# Picobox.net
KiCad netlist of a schematic drawn in EasyEDA
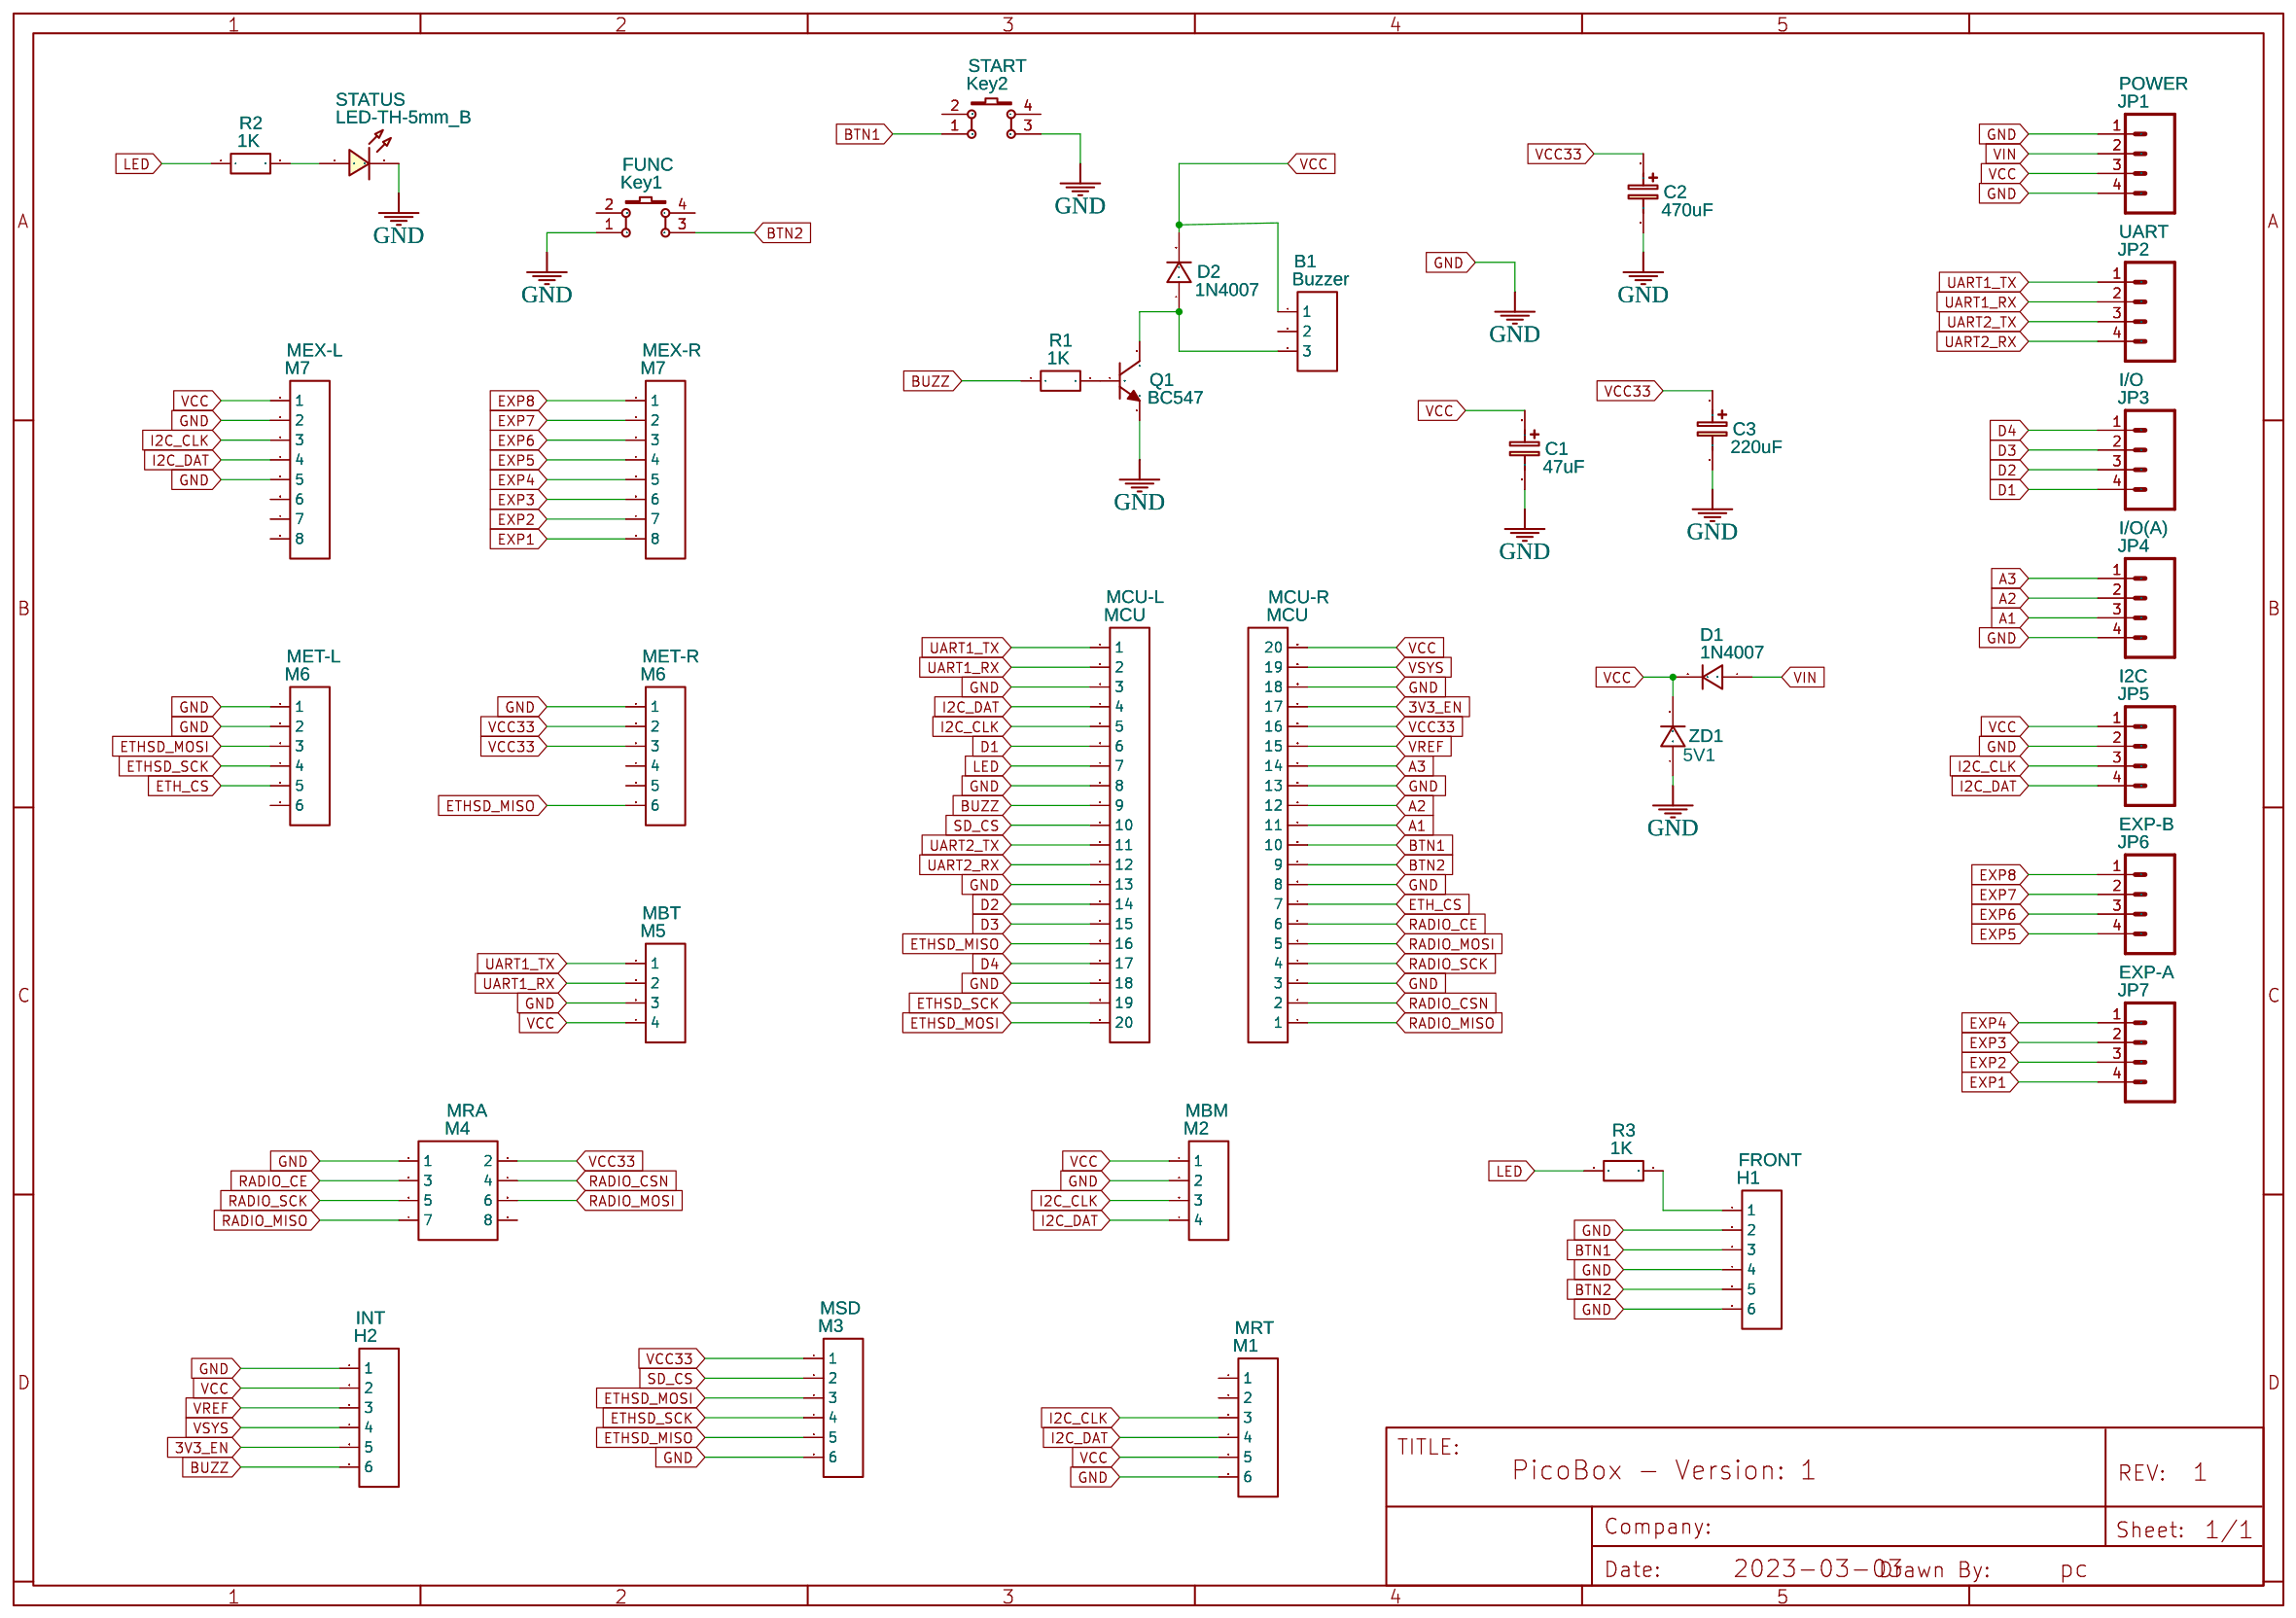
[diagram p0: schematic sheet]

(export (version "E")
  (design (tool "Eeschema 10.0.6"))
  (components
    (comp (ref "B1")
      (value "Buzzer")
      (fields (field (name "BOM_Supplier Part") "C146690"))
      (libsource (lib "") (part "HDR-F-2.54_1x3"))
    )
    (comp (ref "C1") (value "47uF") (libsource (lib "") (part "C_Tan_SMD_A_EU")))
    (comp (ref "C2") (value "470uF") (libsource (lib "") (part "C_Tan_SMD_A_EU")))
    (comp (ref "C3") (value "220uF") (libsource (lib "") (part "C_Tan_SMD_A_EU")))
    (comp (ref "D1")
      (value "1N4007")
      (fields (field (name "BOM_Manufacturer Part") "1N4007W") (field (name "BOM_Supplier Part") "C328592"))
      (libsource (lib "") (part "1N4007W_2"))
    )
    (comp (ref "D2")
      (value "1N4007")
      (fields (field (name "BOM_Manufacturer Part") "1N4007W") (field (name "BOM_Supplier Part") "C328592"))
      (libsource (lib "") (part "1N4007W_1"))
    )
    (comp (ref "EXP-A") (value "JP7") (libsource (lib "") (part "M04SCREW_5")))
    (comp (ref "EXP-B") (value "JP6") (libsource (lib "") (part "M04SCREW_2")))
    (comp (ref "FRONT")
      (value "H1")
      (fields (field (name "BOM_Supplier Part") "C40877"))
      (libsource (lib "") (part "HDR-F-2.54_1x6_3"))
    )
    (comp (ref "FUNC")
      (value "Key1")
      (fields
        (field (name "BOM_Manufacturer Part") "K2-1102DP-E4SW-04")
        (field (name "BOM_Supplier Part") "C136684")
      )
      (libsource (lib "") (part "K4-6×6_TH"))
    )
    (comp (ref "I/O") (value "JP3") (libsource (lib "") (part "M04SCREW_3")))
    (comp (ref "I/O(A)") (value "JP4") (libsource (lib "") (part "M04SCREW")))
    (comp (ref "I2C") (value "JP5") (libsource (lib "") (part "M04SCREW_1")))
    (comp (ref "INT")
      (value "H2")
      (fields (field (name "BOM_Supplier Part") "C40877"))
      (libsource (lib "") (part "HDR-F-2.54_1x6_4"))
    )
    (comp (ref "MBM")
      (value "M2")
      (fields (field (name "BOM_Supplier Part") "C225501"))
      (libsource (lib "") (part "HDR-F-2.54_1x4_1"))
    )
    (comp (ref "MBT")
      (value "M5")
      (fields (field (name "BOM_Supplier Part") "C225501"))
      (libsource (lib "") (part "HDR-F-2.54_1x4"))
    )
    (comp (ref "MCU-L")
      (value "MCU")
      (fields (field (name "BOM_Supplier Part") "C50984"))
      (libsource (lib "") (part "HDR-F-2.54_1x20_1"))
    )
    (comp (ref "MCU-R")
      (value "MCU")
      (fields (field (name "BOM_Supplier Part") "C50984"))
      (libsource (lib "") (part "HDR-F-2.54_1x20"))
    )
    (comp (ref "MET-L")
      (value "M6")
      (fields (field (name "BOM_Supplier Part") "C40877"))
      (libsource (lib "") (part "HDR-F-2.54_1x6_1"))
    )
    (comp (ref "MET-R")
      (value "M6")
      (fields (field (name "BOM_Supplier Part") "C40877"))
      (libsource (lib "") (part "HDR-F-2.54_1x6_5"))
    )
    (comp (ref "MEX-L")
      (value "M7")
      (fields (field (name "BOM_Supplier Part") "C225505"))
      (libsource (lib "") (part "HDR-F-2.54_1x8_1"))
    )
    (comp (ref "MEX-R")
      (value "M7")
      (fields (field (name "BOM_Supplier Part") "C225505"))
      (libsource (lib "") (part "HDR-F-2.54_1x8"))
    )
    (comp (ref "MRA")
      (value "M4")
      (fields (field (name "BOM_Supplier Part") "C239344"))
      (libsource (lib "") (part "HDR-F-2.54_2x4"))
    )
    (comp (ref "MRT")
      (value "M1")
      (fields (field (name "BOM_Supplier Part") "C40877"))
      (libsource (lib "") (part "HDR-F-2.54_1x6"))
    )
    (comp (ref "MSD")
      (value "M3")
      (fields (field (name "BOM_Supplier Part") "C40877"))
      (libsource (lib "") (part "HDR-F-2.54_1x6_2"))
    )
    (comp (ref "POWER") (value "JP1") (libsource (lib "") (part "M04SCREW_6")))
    (comp (ref "Q1")
      (value "BC547")
      (fields
        (field (name "BOM_Manufacturer Part") "2n3904S-RTK/PS")
        (field (name "BOM_Supplier Part") "C18536")
      )
      (libsource (lib "") (part "2N3904(SOT-23)"))
    )
    (comp (ref "R1") (value "1K") (libsource (lib "") (part "R_0603_EU")))
    (comp (ref "R2") (value "1K") (libsource (lib "") (part "R_0603_EU")))
    (comp (ref "R3") (value "1K") (libsource (lib "") (part "R_0603_EU")))
    (comp (ref "START")
      (value "Key2")
      (fields
        (field (name "BOM_Manufacturer Part") "K2-1102DP-E4SW-04")
        (field (name "BOM_Supplier Part") "C136684")
      )
      (libsource (lib "") (part "K4-6×6_TH_1"))
    )
    (comp (ref "STATUS")
      (value "LED-TH-5mm_B")
      (fields
        (field (name "BOM_Manufacturer Part") "333-2SYGD/S530-E2")
        (field (name "BOM_Supplier Part") "C88163")
      )
      (libsource (lib "") (part "LED-TH-5mm_G"))
    )
    (comp (ref "UART") (value "JP2") (libsource (lib "") (part "M04SCREW_4")))
    (comp (ref "ZD1")
      (value "1N4001")
      (fields (field (name "BOM_Manufacturer Part") "1N4007W") (field (name "BOM_Supplier Part") "C328592"))
      (libsource (lib "") (part "1N4007W"))
    )
  )
  (nets
    (net (code "1") (name "3V3_EN") (class "Default")
      (node (ref "INT") (pin "5") (pinfunction "5_5") (pintype "input"))
      (node (ref "MCU-R") (pin "17") (pinfunction "17_17") (pintype "unspecified"))
    )
    (net (code "2") (name "A1") (class "Default")
      (node (ref "I/O(A)") (pin "3") (pinfunction "3_3") (pintype "bidirectional"))
      (node (ref "MCU-R") (pin "11") (pinfunction "11_11") (pintype "unspecified"))
    )
    (net (code "3") (name "A2") (class "Default")
      (node (ref "I/O(A)") (pin "2") (pinfunction "2_2") (pintype "bidirectional"))
      (node (ref "MCU-R") (pin "12") (pinfunction "12_12") (pintype "unspecified"))
    )
    (net (code "4") (name "A3") (class "Default")
      (node (ref "I/O(A)") (pin "1") (pinfunction "1_1") (pintype "bidirectional"))
      (node (ref "MCU-R") (pin "14") (pinfunction "14_14") (pintype "unspecified"))
    )
    (net (code "5") (name "BTN1") (class "Default")
      (node (ref "FRONT") (pin "3") (pinfunction "3_3") (pintype "input"))
      (node (ref "MCU-R") (pin "10") (pinfunction "10_10") (pintype "unspecified"))
      (node (ref "START") (pin "1") (pinfunction "1_1") (pintype "unspecified"))
    )
    (net (code "6") (name "BTN2") (class "Default")
      (node (ref "FRONT") (pin "5") (pinfunction "5_5") (pintype "input"))
      (node (ref "FUNC") (pin "3") (pinfunction "3_3") (pintype "unspecified"))
      (node (ref "MCU-R") (pin "9") (pinfunction "9_9") (pintype "unspecified"))
    )
    (net (code "7") (name "BUZZ") (class "Default")
      (node (ref "INT") (pin "6") (pinfunction "6_6") (pintype "input"))
      (node (ref "MCU-L") (pin "9") (pinfunction "9_9") (pintype "unspecified"))
      (node (ref "R1") (pin "1") (pinfunction "1_1") (pintype "unspecified"))
    )
    (net (code "8") (name "D1") (class "Default")
      (node (ref "I/O") (pin "4") (pinfunction "4_4") (pintype "bidirectional"))
      (node (ref "MCU-L") (pin "6") (pinfunction "6_6") (pintype "unspecified"))
    )
    (net (code "9") (name "D2") (class "Default")
      (node (ref "I/O") (pin "3") (pinfunction "3_3") (pintype "bidirectional"))
      (node (ref "MCU-L") (pin "14") (pinfunction "14_14") (pintype "unspecified"))
    )
    (net (code "10") (name "D3") (class "Default")
      (node (ref "I/O") (pin "2") (pinfunction "2_2") (pintype "bidirectional"))
      (node (ref "MCU-L") (pin "15") (pinfunction "15_15") (pintype "unspecified"))
    )
    (net (code "11") (name "D4") (class "Default")
      (node (ref "I/O") (pin "1") (pinfunction "1_1") (pintype "bidirectional"))
      (node (ref "MCU-L") (pin "17") (pinfunction "17_17") (pintype "unspecified"))
    )
    (net (code "12") (name "ETHSD_MISO") (class "Default")
      (node (ref "MCU-L") (pin "16") (pinfunction "16_16") (pintype "unspecified"))
      (node (ref "MET-R") (pin "6") (pinfunction "6_6") (pintype "input"))
      (node (ref "MSD") (pin "5") (pinfunction "5_5") (pintype "input"))
    )
    (net (code "13") (name "ETHSD_MOSI") (class "Default")
      (node (ref "MCU-L") (pin "20") (pinfunction "20_20") (pintype "unspecified"))
      (node (ref "MET-L") (pin "3") (pinfunction "3_3") (pintype "input"))
      (node (ref "MSD") (pin "3") (pinfunction "3_3") (pintype "input"))
    )
    (net (code "14") (name "ETHSD_SCK") (class "Default")
      (node (ref "MCU-L") (pin "19") (pinfunction "19_19") (pintype "unspecified"))
      (node (ref "MET-L") (pin "4") (pinfunction "4_4") (pintype "input"))
      (node (ref "MSD") (pin "4") (pinfunction "4_4") (pintype "input"))
    )
    (net (code "15") (name "ETH_CS") (class "Default")
      (node (ref "MCU-R") (pin "7") (pinfunction "7_7") (pintype "unspecified"))
      (node (ref "MET-L") (pin "5") (pinfunction "5_5") (pintype "input"))
    )
    (net (code "16") (name "EXP1") (class "Default")
      (node (ref "EXP-A") (pin "4") (pinfunction "4_4") (pintype "bidirectional"))
      (node (ref "MEX-R") (pin "8") (pinfunction "8_8") (pintype "unspecified"))
    )
    (net (code "17") (name "EXP2") (class "Default")
      (node (ref "EXP-A") (pin "3") (pinfunction "3_3") (pintype "bidirectional"))
      (node (ref "MEX-R") (pin "7") (pinfunction "7_7") (pintype "unspecified"))
    )
    (net (code "18") (name "EXP3") (class "Default")
      (node (ref "EXP-A") (pin "2") (pinfunction "2_2") (pintype "bidirectional"))
      (node (ref "MEX-R") (pin "6") (pinfunction "6_6") (pintype "unspecified"))
    )
    (net (code "19") (name "EXP4") (class "Default")
      (node (ref "EXP-A") (pin "1") (pinfunction "1_1") (pintype "bidirectional"))
      (node (ref "MEX-R") (pin "5") (pinfunction "5_5") (pintype "unspecified"))
    )
    (net (code "20") (name "EXP5") (class "Default")
      (node (ref "EXP-B") (pin "4") (pinfunction "4_4") (pintype "bidirectional"))
      (node (ref "MEX-R") (pin "4") (pinfunction "4_4") (pintype "unspecified"))
    )
    (net (code "21") (name "EXP6") (class "Default")
      (node (ref "EXP-B") (pin "3") (pinfunction "3_3") (pintype "bidirectional"))
      (node (ref "MEX-R") (pin "3") (pinfunction "3_3") (pintype "unspecified"))
    )
    (net (code "22") (name "EXP7") (class "Default")
      (node (ref "EXP-B") (pin "2") (pinfunction "2_2") (pintype "bidirectional"))
      (node (ref "MEX-R") (pin "2") (pinfunction "2_2") (pintype "unspecified"))
    )
    (net (code "23") (name "EXP8") (class "Default")
      (node (ref "EXP-B") (pin "1") (pinfunction "1_1") (pintype "bidirectional"))
      (node (ref "MEX-R") (pin "1") (pinfunction "1_1") (pintype "unspecified"))
    )
    (net (code "24") (name "GND") (class "Default")
      (node (ref "C1") (pin "VSS") (pinfunction "2_VSS") (pintype "unspecified"))
      (node (ref "C2") (pin "VSS") (pinfunction "2_VSS") (pintype "unspecified"))
      (node (ref "C3") (pin "VSS") (pinfunction "2_VSS") (pintype "unspecified"))
      (node (ref "FRONT") (pin "2") (pinfunction "2_2") (pintype "input"))
      (node (ref "FRONT") (pin "4") (pinfunction "4_4") (pintype "input"))
      (node (ref "FRONT") (pin "6") (pinfunction "6_6") (pintype "input"))
      (node (ref "FUNC") (pin "1") (pinfunction "1_1") (pintype "unspecified"))
      (node (ref "I/O(A)") (pin "4") (pinfunction "4_4") (pintype "bidirectional"))
      (node (ref "I2C") (pin "2") (pinfunction "2_2") (pintype "bidirectional"))
      (node (ref "INT") (pin "1") (pinfunction "1_1") (pintype "input"))
      (node (ref "MBM") (pin "2") (pinfunction "2_2") (pintype "unspecified"))
      (node (ref "MBT") (pin "3") (pinfunction "3_3") (pintype "unspecified"))
      (node (ref "MCU-L") (pin "13") (pinfunction "13_13") (pintype "unspecified"))
      (node (ref "MCU-L") (pin "18") (pinfunction "18_18") (pintype "unspecified"))
      (node (ref "MCU-L") (pin "3") (pinfunction "3_3") (pintype "unspecified"))
      (node (ref "MCU-L") (pin "8") (pinfunction "8_8") (pintype "unspecified"))
      (node (ref "MCU-R") (pin "13") (pinfunction "13_13") (pintype "unspecified"))
      (node (ref "MCU-R") (pin "18") (pinfunction "18_18") (pintype "unspecified"))
      (node (ref "MCU-R") (pin "3") (pinfunction "3_3") (pintype "unspecified"))
      (node (ref "MCU-R") (pin "8") (pinfunction "8_8") (pintype "unspecified"))
      (node (ref "MET-L") (pin "1") (pinfunction "1_1") (pintype "input"))
      (node (ref "MET-L") (pin "2") (pinfunction "2_2") (pintype "input"))
      (node (ref "MET-R") (pin "1") (pinfunction "1_1") (pintype "input"))
      (node (ref "MEX-L") (pin "2") (pinfunction "2_2") (pintype "unspecified"))
      (node (ref "MEX-L") (pin "5") (pinfunction "5_5") (pintype "unspecified"))
      (node (ref "MRA") (pin "1") (pinfunction "1_1") (pintype "unspecified"))
      (node (ref "MRT") (pin "6") (pinfunction "6_6") (pintype "input"))
      (node (ref "MSD") (pin "6") (pinfunction "6_6") (pintype "input"))
      (node (ref "POWER") (pin "1") (pinfunction "1_1") (pintype "bidirectional"))
      (node (ref "POWER") (pin "4") (pinfunction "4_4") (pintype "bidirectional"))
      (node (ref "Q1") (pin "1") (pinfunction "E_1") (pintype "input"))
      (node (ref "START") (pin "3") (pinfunction "3_3") (pintype "unspecified"))
      (node (ref "STATUS") (pin "2") (pinfunction "2_2") (pintype "unspecified"))
      (node (ref "ZD1") (pin "A") (pinfunction "2_A") (pintype "unspecified"))
    )
    (net (code "25") (name "I2C_CLK") (class "Default")
      (node (ref "I2C") (pin "3") (pinfunction "3_3") (pintype "bidirectional"))
      (node (ref "MBM") (pin "3") (pinfunction "3_3") (pintype "unspecified"))
      (node (ref "MCU-L") (pin "5") (pinfunction "5_5") (pintype "unspecified"))
      (node (ref "MEX-L") (pin "3") (pinfunction "3_3") (pintype "unspecified"))
      (node (ref "MRT") (pin "3") (pinfunction "3_3") (pintype "input"))
    )
    (net (code "26") (name "I2C_DAT") (class "Default")
      (node (ref "I2C") (pin "4") (pinfunction "4_4") (pintype "bidirectional"))
      (node (ref "MBM") (pin "4") (pinfunction "4_4") (pintype "unspecified"))
      (node (ref "MCU-L") (pin "4") (pinfunction "4_4") (pintype "unspecified"))
      (node (ref "MEX-L") (pin "4") (pinfunction "4_4") (pintype "unspecified"))
      (node (ref "MRT") (pin "4") (pinfunction "4_4") (pintype "input"))
    )
    (net (code "27") (name "LED") (class "Default")
      (node (ref "MCU-L") (pin "7") (pinfunction "7_7") (pintype "unspecified"))
      (node (ref "R2") (pin "1") (pinfunction "1_1") (pintype "unspecified"))
      (node (ref "R3") (pin "1") (pinfunction "1_1") (pintype "unspecified"))
    )
    (net (code "28") (name "Net-(B1-3)") (class "Default")
      (node (ref "B1") (pin "2") (pinfunction "3_2") (pintype "input"))
      (node (ref "D2") (pin "A") (pinfunction "2_A") (pintype "unspecified"))
      (node (ref "Q1") (pin "3") (pinfunction "C_3") (pintype "input"))
    )
    (net (code "29") (name "Net-(FRONT-Pad1)") (class "Default")
      (node (ref "FRONT") (pin "1") (pinfunction "1_1") (pintype "input"))
      (node (ref "R3") (pin "2") (pinfunction "2_2") (pintype "unspecified"))
    )
    (net (code "30") (name "Net-(Q1-B)") (class "Default")
      (node (ref "Q1") (pin "2") (pinfunction "B_2") (pintype "input"))
      (node (ref "R1") (pin "2") (pinfunction "2_2") (pintype "unspecified"))
    )
    (net (code "31") (name "Net-(R2-Pad2)") (class "Default")
      (node (ref "R2") (pin "2") (pinfunction "2_2") (pintype "unspecified"))
      (node (ref "STATUS") (pin "1") (pinfunction "1_1") (pintype "unspecified"))
    )
    (net (code "32") (name "RADIO_CE") (class "Default")
      (node (ref "MCU-R") (pin "6") (pinfunction "6_6") (pintype "unspecified"))
      (node (ref "MRA") (pin "3") (pinfunction "3_3") (pintype "unspecified"))
    )
    (net (code "33") (name "RADIO_CSN") (class "Default")
      (node (ref "MCU-R") (pin "2") (pinfunction "2_2") (pintype "unspecified"))
      (node (ref "MRA") (pin "4") (pinfunction "4_4") (pintype "unspecified"))
    )
    (net (code "34") (name "RADIO_MISO") (class "Default")
      (node (ref "MCU-R") (pin "1") (pinfunction "1_1") (pintype "unspecified"))
      (node (ref "MRA") (pin "7") (pinfunction "7_7") (pintype "unspecified"))
    )
    (net (code "35") (name "RADIO_MOSI") (class "Default")
      (node (ref "MCU-R") (pin "5") (pinfunction "5_5") (pintype "unspecified"))
      (node (ref "MRA") (pin "6") (pinfunction "6_6") (pintype "unspecified"))
    )
    (net (code "36") (name "RADIO_SCK") (class "Default")
      (node (ref "MCU-R") (pin "4") (pinfunction "4_4") (pintype "unspecified"))
      (node (ref "MRA") (pin "5") (pinfunction "5_5") (pintype "unspecified"))
    )
    (net (code "37") (name "SD_CS") (class "Default")
      (node (ref "MCU-L") (pin "10") (pinfunction "10_10") (pintype "unspecified"))
      (node (ref "MSD") (pin "2") (pinfunction "2_2") (pintype "input"))
    )
    (net (code "38") (name "UART1_RX") (class "Default")
      (node (ref "MBT") (pin "2") (pinfunction "2_2") (pintype "unspecified"))
      (node (ref "MCU-L") (pin "2") (pinfunction "2_2") (pintype "unspecified"))
      (node (ref "UART") (pin "2") (pinfunction "2_2") (pintype "bidirectional"))
    )
    (net (code "39") (name "UART1_TX") (class "Default")
      (node (ref "MBT") (pin "1") (pinfunction "1_1") (pintype "unspecified"))
      (node (ref "MCU-L") (pin "1") (pinfunction "1_1") (pintype "unspecified"))
      (node (ref "UART") (pin "1") (pinfunction "1_1") (pintype "bidirectional"))
    )
    (net (code "40") (name "UART2_RX") (class "Default")
      (node (ref "MCU-L") (pin "12") (pinfunction "12_12") (pintype "unspecified"))
      (node (ref "UART") (pin "4") (pinfunction "4_4") (pintype "bidirectional"))
    )
    (net (code "41") (name "UART2_TX") (class "Default")
      (node (ref "MCU-L") (pin "11") (pinfunction "11_11") (pintype "unspecified"))
      (node (ref "UART") (pin "3") (pinfunction "3_3") (pintype "bidirectional"))
    )
    (net (code "42") (name "VCC") (class "Default")
      (node (ref "B1") (pin "1") (pinfunction "1_1") (pintype "input"))
      (node (ref "C1") (pin "VDD") (pinfunction "1_VDD") (pintype "unspecified"))
      (node (ref "D1") (pin "C") (pinfunction "1_C") (pintype "unspecified"))
      (node (ref "D2") (pin "C") (pinfunction "1_C") (pintype "unspecified"))
      (node (ref "I2C") (pin "1") (pinfunction "1_1") (pintype "bidirectional"))
      (node (ref "INT") (pin "2") (pinfunction "2_2") (pintype "input"))
      (node (ref "MBM") (pin "1") (pinfunction "1_1") (pintype "unspecified"))
      (node (ref "MBT") (pin "4") (pinfunction "4_4") (pintype "unspecified"))
      (node (ref "MCU-R") (pin "20") (pinfunction "20_20") (pintype "unspecified"))
      (node (ref "MEX-L") (pin "1") (pinfunction "1_1") (pintype "unspecified"))
      (node (ref "MRT") (pin "5") (pinfunction "5_5") (pintype "input"))
      (node (ref "POWER") (pin "3") (pinfunction "3_3") (pintype "bidirectional"))
      (node (ref "ZD1") (pin "C") (pinfunction "1_C") (pintype "unspecified"))
    )
    (net (code "43") (name "VCC33") (class "Default")
      (node (ref "C2") (pin "VDD") (pinfunction "1_VDD") (pintype "unspecified"))
      (node (ref "C3") (pin "VDD") (pinfunction "1_VDD") (pintype "unspecified"))
      (node (ref "MCU-R") (pin "16") (pinfunction "16_16") (pintype "unspecified"))
      (node (ref "MET-R") (pin "2") (pinfunction "2_2") (pintype "input"))
      (node (ref "MET-R") (pin "3") (pinfunction "3_3") (pintype "input"))
      (node (ref "MRA") (pin "2") (pinfunction "2_2") (pintype "unspecified"))
      (node (ref "MSD") (pin "1") (pinfunction "1_1") (pintype "input"))
    )
    (net (code "44") (name "VIN") (class "Default")
      (node (ref "D1") (pin "A") (pinfunction "2_A") (pintype "unspecified"))
      (node (ref "POWER") (pin "2") (pinfunction "2_2") (pintype "bidirectional"))
    )
    (net (code "45") (name "VREF") (class "Default")
      (node (ref "INT") (pin "3") (pinfunction "3_3") (pintype "input"))
      (node (ref "MCU-R") (pin "15") (pinfunction "15_15") (pintype "unspecified"))
    )
    (net (code "46") (name "VSYS") (class "Default")
      (node (ref "INT") (pin "4") (pinfunction "4_4") (pintype "input"))
      (node (ref "MCU-R") (pin "19") (pinfunction "19_19") (pintype "unspecified"))
    )
    (net (code "47") (name "unconnected-(B1-Pad2)") (class "Default")
      (node (ref "B1") (pin "2") (pinfunction "2_2") (pintype "input"))
    )
    (net (code "48") (name "unconnected-(FUNC-Pad2)") (class "Default")
      (node (ref "FUNC") (pin "2") (pinfunction "2_2") (pintype "unspecified"))
    )
    (net (code "49") (name "unconnected-(FUNC-Pad4)") (class "Default")
      (node (ref "FUNC") (pin "4") (pinfunction "4_4") (pintype "unspecified"))
    )
    (net (code "50") (name "unconnected-(MET-L-Pad6)") (class "Default")
      (node (ref "MET-L") (pin "6") (pinfunction "6_6") (pintype "input"))
    )
    (net (code "51") (name "unconnected-(MET-R-Pad4)") (class "Default")
      (node (ref "MET-R") (pin "4") (pinfunction "4_4") (pintype "input"))
    )
    (net (code "52") (name "unconnected-(MET-R-Pad5)") (class "Default")
      (node (ref "MET-R") (pin "5") (pinfunction "5_5") (pintype "input"))
    )
    (net (code "53") (name "unconnected-(MEX-L-Pad6)") (class "Default")
      (node (ref "MEX-L") (pin "6") (pinfunction "6_6") (pintype "unspecified"))
    )
    (net (code "54") (name "unconnected-(MEX-L-Pad7)") (class "Default")
      (node (ref "MEX-L") (pin "7") (pinfunction "7_7") (pintype "unspecified"))
    )
    (net (code "55") (name "unconnected-(MEX-L-Pad8)") (class "Default")
      (node (ref "MEX-L") (pin "8") (pinfunction "8_8") (pintype "unspecified"))
    )
    (net (code "56") (name "unconnected-(MRA-Pad8)") (class "Default")
      (node (ref "MRA") (pin "8") (pinfunction "8_8") (pintype "unspecified"))
    )
    (net (code "57") (name "unconnected-(MRT-Pad1)") (class "Default")
      (node (ref "MRT") (pin "1") (pinfunction "1_1") (pintype "input"))
    )
    (net (code "58") (name "unconnected-(MRT-Pad2)") (class "Default")
      (node (ref "MRT") (pin "2") (pinfunction "2_2") (pintype "input"))
    )
    (net (code "59") (name "unconnected-(START-Pad2)") (class "Default")
      (node (ref "START") (pin "2") (pinfunction "2_2") (pintype "unspecified"))
    )
    (net (code "60") (name "unconnected-(START-Pad4)") (class "Default")
      (node (ref "START") (pin "4") (pinfunction "4_4") (pintype "unspecified"))
    )
  )
)
